# 01_POWER.net
KiCad netlist of a schematic drawn in Altium Designer
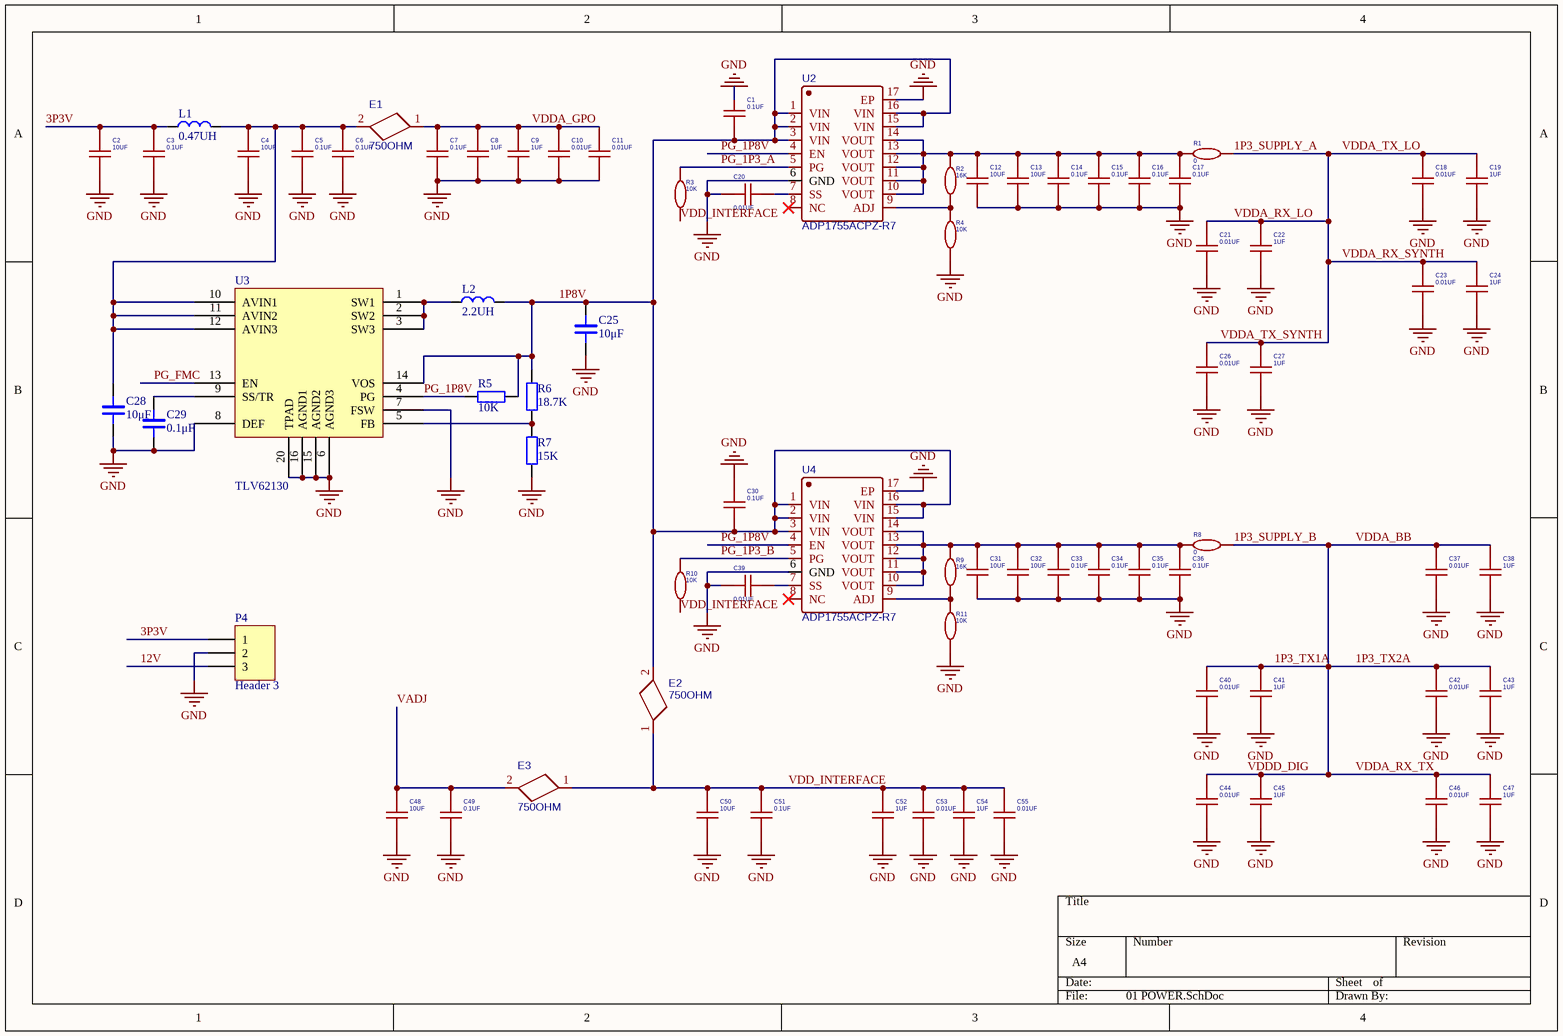
[diagram p0: 01 POWER.SchDoc]

(export (version "E")
  (design (tool "Eeschema 10.0.6"))
  (components
    (comp (ref "C1")
      (value "0.1UF")
      (footprint "C0402")
      (fields
        (field (name "BOM_MANUFACTURER PART") "0402B104K160")
        (field (name "BOM_SUPPLIER PART") "C83056")
      )
      (libsource (lib "pluto-7020CLG400") (part "0.1UF"))
    )
    (comp (ref "C2")
      (value "10UF")
      (footprint "C0402")
      (fields
        (field (name "BOM_MANUFACTURER PART") "0402B104K160")
        (field (name "BOM_SUPPLIER PART") "C83056")
      )
      (libsource (lib "pluto-7020CLG400") (part "10UF"))
    )
    (comp (ref "C3")
      (value "0.1UF")
      (footprint "C0402")
      (fields
        (field (name "BOM_MANUFACTURER PART") "0402B104K160")
        (field (name "BOM_SUPPLIER PART") "C83056")
      )
      (libsource (lib "pluto-7020CLG400") (part "0.1UF"))
    )
    (comp (ref "C4")
      (value "10UF")
      (footprint "C0402")
      (fields
        (field (name "BOM_MANUFACTURER PART") "0402B104K160")
        (field (name "BOM_SUPPLIER PART") "C83056")
      )
      (libsource (lib "pluto-7020CLG400") (part "10UF"))
    )
    (comp (ref "C5")
      (value "0.1UF")
      (footprint "C0402")
      (fields
        (field (name "BOM_MANUFACTURER PART") "0402B104K160")
        (field (name "BOM_SUPPLIER PART") "C83056")
      )
      (libsource (lib "pluto-7020CLG400") (part "0.1UF"))
    )
    (comp (ref "C6")
      (value "0.1UF")
      (footprint "C0402")
      (fields
        (field (name "BOM_MANUFACTURER PART") "0402B104K160")
        (field (name "BOM_SUPPLIER PART") "C83056")
      )
      (libsource (lib "pluto-7020CLG400") (part "0.1UF"))
    )
    (comp (ref "C7")
      (value "0.1UF")
      (footprint "C0402")
      (fields
        (field (name "BOM_MANUFACTURER PART") "0402B104K160")
        (field (name "BOM_SUPPLIER PART") "C83056")
      )
      (libsource (lib "pluto-7020CLG400") (part "0.1UF"))
    )
    (comp (ref "C8")
      (value "1UF")
      (footprint "C0402")
      (fields
        (field (name "BOM_MANUFACTURER PART") "0402B104K160")
        (field (name "BOM_SUPPLIER PART") "C83056")
      )
      (libsource (lib "pluto-7020CLG400") (part "10UF"))
    )
    (comp (ref "C9")
      (value "1UF")
      (footprint "C0402")
      (fields
        (field (name "BOM_MANUFACTURER PART") "0402B104K160")
        (field (name "BOM_SUPPLIER PART") "C83056")
      )
      (libsource (lib "pluto-7020CLG400") (part "10UF"))
    )
    (comp (ref "C10")
      (value "0.01UF")
      (footprint "C0201")
      (fields
        (field (name "BOM_MANUFACTURER PART") "0402B104K160")
        (field (name "BOM_SUPPLIER PART") "C83056")
      )
      (libsource (lib "pluto-7020CLG400") (part "10UF"))
    )
    (comp (ref "C11")
      (value "0.01UF")
      (footprint "C0201")
      (fields
        (field (name "BOM_MANUFACTURER PART") "0402B104K160")
        (field (name "BOM_SUPPLIER PART") "C83056")
      )
      (libsource (lib "pluto-7020CLG400") (part "10UF"))
    )
    (comp (ref "C12")
      (value "10UF")
      (footprint "C0402")
      (fields
        (field (name "BOM_MANUFACTURER PART") "0402B104K160")
        (field (name "BOM_SUPPLIER PART") "C83056")
      )
      (libsource (lib "pluto-7020CLG400") (part "10UF"))
    )
    (comp (ref "C13")
      (value "10UF")
      (footprint "C0402")
      (fields
        (field (name "BOM_MANUFACTURER PART") "0402B104K160")
        (field (name "BOM_SUPPLIER PART") "C83056")
      )
      (libsource (lib "pluto-7020CLG400") (part "10UF"))
    )
    (comp (ref "C14")
      (value "0.1UF")
      (footprint "C0402")
      (fields
        (field (name "BOM_MANUFACTURER PART") "0402B104K160")
        (field (name "BOM_SUPPLIER PART") "C83056")
      )
      (libsource (lib "pluto-7020CLG400") (part "0.1UF"))
    )
    (comp (ref "C15")
      (value "0.1UF")
      (footprint "C0402")
      (fields
        (field (name "BOM_MANUFACTURER PART") "0402B104K160")
        (field (name "BOM_SUPPLIER PART") "C83056")
      )
      (libsource (lib "pluto-7020CLG400") (part "0.1UF"))
    )
    (comp (ref "C16")
      (value "0.1UF")
      (footprint "C0402")
      (fields
        (field (name "BOM_MANUFACTURER PART") "0402B104K160")
        (field (name "BOM_SUPPLIER PART") "C83056")
      )
      (libsource (lib "pluto-7020CLG400") (part "0.1UF"))
    )
    (comp (ref "C17")
      (value "0.1UF")
      (footprint "C0402")
      (fields
        (field (name "BOM_MANUFACTURER PART") "0402B104K160")
        (field (name "BOM_SUPPLIER PART") "C83056")
      )
      (libsource (lib "pluto-7020CLG400") (part "0.1UF"))
    )
    (comp (ref "C18")
      (value "0.01UF")
      (footprint "C0201")
      (fields
        (field (name "BOM_MANUFACTURER PART") "0402B104K160")
        (field (name "BOM_SUPPLIER PART") "C83056")
      )
      (libsource (lib "pluto-7020CLG400") (part "10UF"))
    )
    (comp (ref "C19")
      (value "1UF")
      (footprint "C0402")
      (fields
        (field (name "BOM_MANUFACTURER PART") "0402B104K160")
        (field (name "BOM_SUPPLIER PART") "C83056")
      )
      (libsource (lib "pluto-7020CLG400") (part "10UF"))
    )
    (comp (ref "C20")
      (value "0.01UF")
      (footprint "C0201")
      (fields
        (field (name "BOM_MANUFACTURER PART") "0402B104K160")
        (field (name "BOM_SUPPLIER PART") "C83056")
      )
      (libsource (lib "pluto-7020CLG400") (part "0.01UF"))
    )
    (comp (ref "C21")
      (value "0.01UF")
      (footprint "C0201")
      (fields
        (field (name "BOM_MANUFACTURER PART") "0402B104K160")
        (field (name "BOM_SUPPLIER PART") "C83056")
      )
      (libsource (lib "pluto-7020CLG400") (part "10UF"))
    )
    (comp (ref "C22")
      (value "1UF")
      (footprint "C0402")
      (fields
        (field (name "BOM_MANUFACTURER PART") "0402B104K160")
        (field (name "BOM_SUPPLIER PART") "C83056")
      )
      (libsource (lib "pluto-7020CLG400") (part "10UF"))
    )
    (comp (ref "C23")
      (value "0.01UF")
      (footprint "C0201")
      (fields
        (field (name "BOM_MANUFACTURER PART") "0402B104K160")
        (field (name "BOM_SUPPLIER PART") "C83056")
      )
      (libsource (lib "pluto-7020CLG400") (part "10UF"))
    )
    (comp (ref "C24")
      (value "1UF")
      (footprint "C0402")
      (fields
        (field (name "BOM_MANUFACTURER PART") "0402B104K160")
        (field (name "BOM_SUPPLIER PART") "C83056")
      )
      (libsource (lib "pluto-7020CLG400") (part "10UF"))
    )
    (comp (ref "C25")
      (value "10μF")
      (footprint "C0402")
      (description "Capacitor")
      (libsource (lib "NGFF_M_Key_xc7z010-clg400") (part "CAP_3"))
    )
    (comp (ref "C26")
      (value "0.01UF")
      (footprint "C0201")
      (fields
        (field (name "BOM_MANUFACTURER PART") "0402B104K160")
        (field (name "BOM_SUPPLIER PART") "C83056")
      )
      (libsource (lib "pluto-7020CLG400") (part "10UF"))
    )
    (comp (ref "C27")
      (value "1UF")
      (footprint "C0402")
      (fields
        (field (name "BOM_MANUFACTURER PART") "0402B104K160")
        (field (name "BOM_SUPPLIER PART") "C83056")
      )
      (libsource (lib "pluto-7020CLG400") (part "10UF"))
    )
    (comp (ref "C28")
      (value "10μF")
      (footprint "C0402")
      (description "Capacitor")
      (libsource (lib "NGFF_M_Key_xc7z010-clg400") (part "CAP_3"))
    )
    (comp (ref "C29")
      (value "0.1μF")
      (footprint "C0402")
      (description "Capacitor")
      (libsource (lib "NGFF_M_Key_xc7z010-clg400") (part "CAP_3"))
    )
    (comp (ref "C30")
      (value "0.1UF")
      (footprint "C0402")
      (fields
        (field (name "BOM_MANUFACTURER PART") "0402B104K160")
        (field (name "BOM_SUPPLIER PART") "C83056")
      )
      (libsource (lib "pluto-7020CLG400") (part "0.1UF"))
    )
    (comp (ref "C31")
      (value "10UF")
      (footprint "C0402")
      (fields
        (field (name "BOM_MANUFACTURER PART") "0402B104K160")
        (field (name "BOM_SUPPLIER PART") "C83056")
      )
      (libsource (lib "pluto-7020CLG400") (part "10UF"))
    )
    (comp (ref "C32")
      (value "10UF")
      (footprint "C0402")
      (fields
        (field (name "BOM_MANUFACTURER PART") "0402B104K160")
        (field (name "BOM_SUPPLIER PART") "C83056")
      )
      (libsource (lib "pluto-7020CLG400") (part "10UF"))
    )
    (comp (ref "C33")
      (value "0.1UF")
      (footprint "C0402")
      (fields
        (field (name "BOM_MANUFACTURER PART") "0402B104K160")
        (field (name "BOM_SUPPLIER PART") "C83056")
      )
      (libsource (lib "pluto-7020CLG400") (part "0.1UF"))
    )
    (comp (ref "C34")
      (value "0.1UF")
      (footprint "C0402")
      (fields
        (field (name "BOM_MANUFACTURER PART") "0402B104K160")
        (field (name "BOM_SUPPLIER PART") "C83056")
      )
      (libsource (lib "pluto-7020CLG400") (part "0.1UF"))
    )
    (comp (ref "C35")
      (value "0.1UF")
      (footprint "C0402")
      (fields
        (field (name "BOM_MANUFACTURER PART") "0402B104K160")
        (field (name "BOM_SUPPLIER PART") "C83056")
      )
      (libsource (lib "pluto-7020CLG400") (part "0.1UF"))
    )
    (comp (ref "C36")
      (value "0.1UF")
      (footprint "C0402")
      (fields
        (field (name "BOM_MANUFACTURER PART") "0402B104K160")
        (field (name "BOM_SUPPLIER PART") "C83056")
      )
      (libsource (lib "pluto-7020CLG400") (part "0.1UF"))
    )
    (comp (ref "C37")
      (value "0.01UF")
      (footprint "C0402")
      (fields
        (field (name "BOM_MANUFACTURER PART") "0402B104K160")
        (field (name "BOM_SUPPLIER PART") "C83056")
      )
      (libsource (lib "pluto-7020CLG400") (part "10UF"))
    )
    (comp (ref "C38")
      (value "1UF")
      (footprint "C0402")
      (fields
        (field (name "BOM_MANUFACTURER PART") "0402B104K160")
        (field (name "BOM_SUPPLIER PART") "C83056")
      )
      (libsource (lib "pluto-7020CLG400") (part "10UF"))
    )
    (comp (ref "C39")
      (value "0.01UF")
      (footprint "C0402")
      (fields
        (field (name "BOM_MANUFACTURER PART") "0402B104K160")
        (field (name "BOM_SUPPLIER PART") "C83056")
      )
      (libsource (lib "pluto-7020CLG400") (part "0.01UF"))
    )
    (comp (ref "C40")
      (value "0.01UF")
      (footprint "C0402")
      (fields
        (field (name "BOM_MANUFACTURER PART") "0402B104K160")
        (field (name "BOM_SUPPLIER PART") "C83056")
      )
      (libsource (lib "pluto-7020CLG400") (part "10UF"))
    )
    (comp (ref "C41")
      (value "1UF")
      (footprint "C0402")
      (fields
        (field (name "BOM_MANUFACTURER PART") "0402B104K160")
        (field (name "BOM_SUPPLIER PART") "C83056")
      )
      (libsource (lib "pluto-7020CLG400") (part "10UF"))
    )
    (comp (ref "C42")
      (value "0.01UF")
      (footprint "C0201")
      (fields
        (field (name "BOM_MANUFACTURER PART") "0402B104K160")
        (field (name "BOM_SUPPLIER PART") "C83056")
      )
      (libsource (lib "pluto-7020CLG400") (part "10UF"))
    )
    (comp (ref "C43")
      (value "1UF")
      (footprint "C0402")
      (fields
        (field (name "BOM_MANUFACTURER PART") "0402B104K160")
        (field (name "BOM_SUPPLIER PART") "C83056")
      )
      (libsource (lib "pluto-7020CLG400") (part "10UF"))
    )
    (comp (ref "C44")
      (value "0.01UF")
      (footprint "C0201")
      (fields
        (field (name "BOM_MANUFACTURER PART") "0402B104K160")
        (field (name "BOM_SUPPLIER PART") "C83056")
      )
      (libsource (lib "pluto-7020CLG400") (part "10UF"))
    )
    (comp (ref "C45")
      (value "1UF")
      (footprint "C0402")
      (fields
        (field (name "BOM_MANUFACTURER PART") "0402B104K160")
        (field (name "BOM_SUPPLIER PART") "C83056")
      )
      (libsource (lib "pluto-7020CLG400") (part "10UF"))
    )
    (comp (ref "C46")
      (value "0.01UF")
      (footprint "C0402")
      (fields
        (field (name "BOM_MANUFACTURER PART") "0402B104K160")
        (field (name "BOM_SUPPLIER PART") "C83056")
      )
      (libsource (lib "pluto-7020CLG400") (part "10UF"))
    )
    (comp (ref "C47")
      (value "1UF")
      (footprint "C0402")
      (fields
        (field (name "BOM_MANUFACTURER PART") "0402B104K160")
        (field (name "BOM_SUPPLIER PART") "C83056")
      )
      (libsource (lib "pluto-7020CLG400") (part "10UF"))
    )
    (comp (ref "C48")
      (value "10UF")
      (footprint "C0603")
      (fields
        (field (name "BOM_MANUFACTURER PART") "0402B104K160")
        (field (name "BOM_SUPPLIER PART") "C83056")
      )
      (libsource (lib "pluto-7020CLG400") (part "10UF"))
    )
    (comp (ref "C49")
      (value "0.1UF")
      (footprint "C0402")
      (fields
        (field (name "BOM_MANUFACTURER PART") "0402B104K160")
        (field (name "BOM_SUPPLIER PART") "C83056")
      )
      (libsource (lib "pluto-7020CLG400") (part "0.1UF"))
    )
    (comp (ref "C50")
      (value "10UF")
      (footprint "C0402")
      (fields
        (field (name "BOM_MANUFACTURER PART") "0402B104K160")
        (field (name "BOM_SUPPLIER PART") "C83056")
      )
      (libsource (lib "pluto-7020CLG400") (part "10UF"))
    )
    (comp (ref "C51")
      (value "0.1UF")
      (footprint "C0201")
      (fields
        (field (name "BOM_MANUFACTURER PART") "0402B104K160")
        (field (name "BOM_SUPPLIER PART") "C83056")
      )
      (libsource (lib "pluto-7020CLG400") (part "0.1UF"))
    )
    (comp (ref "C52")
      (value "1UF")
      (footprint "C0402")
      (fields
        (field (name "BOM_MANUFACTURER PART") "0402B104K160")
        (field (name "BOM_SUPPLIER PART") "C83056")
      )
      (libsource (lib "pluto-7020CLG400") (part "10UF"))
    )
    (comp (ref "C53")
      (value "0.01UF")
      (footprint "C0201")
      (fields
        (field (name "BOM_MANUFACTURER PART") "0402B104K160")
        (field (name "BOM_SUPPLIER PART") "C83056")
      )
      (libsource (lib "pluto-7020CLG400") (part "10UF"))
    )
    (comp (ref "C54")
      (value "1UF")
      (footprint "C0402")
      (fields
        (field (name "BOM_MANUFACTURER PART") "0402B104K160")
        (field (name "BOM_SUPPLIER PART") "C83056")
      )
      (libsource (lib "pluto-7020CLG400") (part "10UF"))
    )
    (comp (ref "C55")
      (value "0.01UF")
      (footprint "C0201")
      (fields
        (field (name "BOM_MANUFACTURER PART") "0402B104K160")
        (field (name "BOM_SUPPLIER PART") "C83056")
      )
      (libsource (lib "pluto-7020CLG400") (part "10UF"))
    )
    (comp (ref "E1")
      (value "750OHM")
      (footprint "L0402")
      (fields (field (name "BOM_MANUFACTURER PART") "BLM21PG221SN1x") (field (name "CONTRIBUTOR") "prophetC"))
      (libsource (lib "pluto-7020CLG400") (part "100OHM"))
    )
    (comp (ref "E2")
      (value "750OHM")
      (footprint "L0402")
      (fields (field (name "BOM_MANUFACTURER PART") "BLM21PG221SN1x") (field (name "CONTRIBUTOR") "prophetC"))
      (libsource (lib "pluto-7020CLG400") (part "100OHM"))
    )
    (comp (ref "E3")
      (value "750OHM")
      (footprint "L0402")
      (fields (field (name "BOM_MANUFACTURER PART") "BLM21PG221SN1x") (field (name "CONTRIBUTOR") "prophetC"))
      (libsource (lib "pluto-7020CLG400") (part "100OHM"))
    )
    (comp (ref "L1")
      (value "0.47UH")
      (footprint "L1008")
      (description "Inductance")
      (libsource (lib "NGFF_M_Key_xc7z010-clg400") (part "INDUCTANCE_1"))
    )
    (comp (ref "L2")
      (value "2.2UH")
      (footprint "L1008")
      (description "Inductance")
      (libsource (lib "NGFF_M_Key_xc7z010-clg400") (part "INDUCTANCE_1"))
    )
    (comp (ref "P4")
      (value "Header 3")
      (footprint "CNBERG1X3H205LD36")
      (description "Header, 3-Pin")
      (fields (field (name "PUBLISHER") "Altium Limited"))
      (libsource (lib "Miscellaneous Connectors") (part "Header 3"))
    )
    (comp (ref "R1")
      (value "0")
      (footprint "R1206")
      (fields
        (field (name "BOM_SUPPLIER PART") "C185392")
        (field (name "BOM_MANUFACTURER PART") "RC0402FR-0780R6L")
        (field (name "CONTRIBUTOR") "LCSC")
      )
      (libsource (lib "pluto-7020CLG400") (part "1"))
    )
    (comp (ref "R2")
      (value "16K")
      (footprint "LC-0402_R")
      (fields
        (field (name "BOM_SUPPLIER PART") "C185392")
        (field (name "BOM_MANUFACTURER PART") "RC0402FR-0780R6L")
        (field (name "CONTRIBUTOR") "LCSC")
      )
      (libsource (lib "pluto-7020CLG400") (part "10K"))
    )
    (comp (ref "R3")
      (value "10K")
      (footprint "C0201")
      (fields
        (field (name "BOM_SUPPLIER PART") "C185392")
        (field (name "BOM_MANUFACTURER PART") "RC0402FR-0780R6L")
        (field (name "CONTRIBUTOR") "LCSC")
      )
      (libsource (lib "pluto-7020CLG400") (part "10K"))
    )
    (comp (ref "R4")
      (value "10K")
      (footprint "LC-0402_R")
      (fields
        (field (name "BOM_SUPPLIER PART") "C185392")
        (field (name "BOM_MANUFACTURER PART") "RC0402FR-0780R6L")
        (field (name "CONTRIBUTOR") "LCSC")
      )
      (libsource (lib "pluto-7020CLG400") (part "10K"))
    )
    (comp (ref "R5")
      (value "10K")
      (footprint "LC-0402_R")
      (description "Resistor")
      (libsource (lib "NGFF_M_Key_xc7z010-clg400") (part "RES"))
    )
    (comp (ref "R6")
      (value "18.7K")
      (footprint "LC-0402_R")
      (description "Resistor")
      (libsource (lib "") (part "RES_1"))
    )
    (comp (ref "R7")
      (value "15K")
      (footprint "LC-0402_R")
      (description "Resistor")
      (libsource (lib "") (part "RES_1"))
    )
    (comp (ref "R8")
      (value "0")
      (footprint "R1206")
      (fields
        (field (name "BOM_SUPPLIER PART") "C185392")
        (field (name "BOM_MANUFACTURER PART") "RC0402FR-0780R6L")
        (field (name "CONTRIBUTOR") "LCSC")
      )
      (libsource (lib "pluto-7020CLG400") (part "1"))
    )
    (comp (ref "R9")
      (value "16K")
      (footprint "LC-0402_R")
      (fields
        (field (name "BOM_SUPPLIER PART") "C185392")
        (field (name "BOM_MANUFACTURER PART") "RC0402FR-0780R6L")
        (field (name "CONTRIBUTOR") "LCSC")
      )
      (libsource (lib "pluto-7020CLG400") (part "10K"))
    )
    (comp (ref "R10")
      (value "10K")
      (footprint "LC-0402_R")
      (fields
        (field (name "BOM_SUPPLIER PART") "C185392")
        (field (name "BOM_MANUFACTURER PART") "RC0402FR-0780R6L")
        (field (name "CONTRIBUTOR") "LCSC")
      )
      (libsource (lib "pluto-7020CLG400") (part "10K"))
    )
    (comp (ref "R11")
      (value "10K")
      (footprint "LC-0402_R")
      (fields
        (field (name "BOM_SUPPLIER PART") "C185392")
        (field (name "BOM_MANUFACTURER PART") "RC0402FR-0780R6L")
        (field (name "CONTRIBUTOR") "LCSC")
      )
      (libsource (lib "pluto-7020CLG400") (part "10K"))
    )
    (comp (ref "U2")
      (value "ADP1755ACPZ-R7")
      (footprint "LFCSP-WQ-16_L4.0-W4.0-P0.65-EP2.3-BL-EP")
      (fields (field (name "BOM_SUPPLIER PART") "C403695") (field (name "CONTRIBUTOR") "LCSC"))
      (libsource (lib "demo_fmccomms3") (part "ADP1755ACPZ-R7"))
    )
    (comp (ref "U3")
      (value "TLV62130")
      (footprint "TLV62130RGT")
      (libsource (lib "PCB_Project") (part "TLV62130"))
    )
    (comp (ref "U4")
      (value "ADP1755ACPZ-R7")
      (footprint "LFCSP-WQ-16_L4.0-W4.0-P0.65-EP2.3-BL-EP")
      (fields (field (name "BOM_SUPPLIER PART") "C403695") (field (name "CONTRIBUTOR") "LCSC"))
      (libsource (lib "demo_fmccomms3") (part "ADP1755ACPZ-R7"))
    )
  )
  (nets
    (net (code "1") (name "/1P3_SUPPLY_A") (class "Default")
      (node (ref "C18") (pin "1") (pinfunction "1_1") (pintype "passive"))
      (node (ref "C19") (pin "1") (pinfunction "1_1") (pintype "passive"))
      (node (ref "C21") (pin "1") (pinfunction "1_1") (pintype "passive"))
      (node (ref "C22") (pin "1") (pinfunction "1_1") (pintype "passive"))
      (node (ref "C23") (pin "1") (pinfunction "1_1") (pintype "passive"))
      (node (ref "C24") (pin "1") (pinfunction "1_1") (pintype "passive"))
      (node (ref "C26") (pin "1") (pinfunction "1_1") (pintype "passive"))
      (node (ref "C27") (pin "1") (pinfunction "1_1") (pintype "passive"))
      (node (ref "R1") (pin "2") (pinfunction "2_2") (pintype "passive"))
    )
    (net (code "2") (name "/1P3_SUPPLY_B") (class "Default")
      (node (ref "C37") (pin "1") (pinfunction "1_1") (pintype "passive"))
      (node (ref "C38") (pin "1") (pinfunction "1_1") (pintype "passive"))
      (node (ref "C40") (pin "1") (pinfunction "1_1") (pintype "passive"))
      (node (ref "C41") (pin "1") (pinfunction "1_1") (pintype "passive"))
      (node (ref "C42") (pin "1") (pinfunction "1_1") (pintype "passive"))
      (node (ref "C43") (pin "1") (pinfunction "1_1") (pintype "passive"))
      (node (ref "C44") (pin "1") (pinfunction "1_1") (pintype "passive"))
      (node (ref "C45") (pin "1") (pinfunction "1_1") (pintype "passive"))
      (node (ref "C46") (pin "1") (pinfunction "1_1") (pintype "passive"))
      (node (ref "C47") (pin "1") (pinfunction "1_1") (pintype "passive"))
      (node (ref "R8") (pin "2") (pinfunction "2_2") (pintype "passive"))
    )
    (net (code "3") (name "/1P8V") (class "Default")
      (node (ref "C1") (pin "2") (pinfunction "2_2") (pintype "passive"))
      (node (ref "C25") (pin "2") (pinfunction "2_2") (pintype "passive"))
      (node (ref "C30") (pin "2") (pinfunction "2_2") (pintype "passive"))
      (node (ref "E2") (pin "2") (pinfunction "2_2") (pintype "passive"))
      (node (ref "L2") (pin "2") (pinfunction "2_2") (pintype "passive"))
      (node (ref "R5") (pin "1") (pinfunction "1_1") (pintype "passive"))
      (node (ref "R6") (pin "1") (pinfunction "1_1") (pintype "passive"))
      (node (ref "U2") (pin "1") (pinfunction "VIN_1") (pintype "passive"))
      (node (ref "U2") (pin "15") (pinfunction "VIN_15") (pintype "passive"))
      (node (ref "U2") (pin "16") (pinfunction "VIN_16") (pintype "passive"))
      (node (ref "U2") (pin "2") (pinfunction "VIN_2") (pintype "passive"))
      (node (ref "U2") (pin "3") (pinfunction "VIN_3") (pintype "passive"))
      (node (ref "U3") (pin "14") (pinfunction "VOS_14") (pintype "passive"))
      (node (ref "U4") (pin "1") (pinfunction "VIN_1") (pintype "passive"))
      (node (ref "U4") (pin "15") (pinfunction "VIN_15") (pintype "passive"))
      (node (ref "U4") (pin "16") (pinfunction "VIN_16") (pintype "passive"))
      (node (ref "U4") (pin "2") (pinfunction "VIN_2") (pintype "passive"))
      (node (ref "U4") (pin "3") (pinfunction "VIN_3") (pintype "passive"))
    )
    (net (code "4") (name "/3P3V") (class "Default")
      (node (ref "C2") (pin "1") (pinfunction "1_1") (pintype "passive"))
      (node (ref "C3") (pin "1") (pinfunction "1_1") (pintype "passive"))
      (node (ref "L1") (pin "1") (pinfunction "1_1") (pintype "passive"))
      (node (ref "P4") (pin "1") (pinfunction "1_1") (pintype "passive"))
    )
    (net (code "5") (name "/12V") (class "Default")
      (node (ref "P4") (pin "3") (pinfunction "3_3") (pintype "passive"))
    )
    (net (code "6") (name "/PG_1P3_A") (class "Default")
      (node (ref "R3") (pin "2") (pinfunction "2_2") (pintype "passive"))
      (node (ref "U2") (pin "5") (pinfunction "PG_5") (pintype "passive"))
    )
    (net (code "7") (name "/PG_1P3_B") (class "Default")
      (node (ref "R10") (pin "2") (pinfunction "2_2") (pintype "passive"))
      (node (ref "U4") (pin "5") (pinfunction "PG_5") (pintype "passive"))
    )
    (net (code "8") (name "/PG_1P8V") (class "Default")
      (node (ref "R5") (pin "2") (pinfunction "2_2") (pintype "passive"))
      (node (ref "U2") (pin "4") (pinfunction "EN_4") (pintype "passive"))
      (node (ref "U3") (pin "4") (pinfunction "PG_4") (pintype "passive"))
      (node (ref "U4") (pin "4") (pinfunction "EN_4") (pintype "passive"))
    )
    (net (code "9") (name "/PG_FMC") (class "Default")
      (node (ref "U3") (pin "13") (pinfunction "EN_13") (pintype "passive"))
    )
    (net (code "10") (name "/VADJ") (class "Default")
      (node (ref "C48") (pin "1") (pinfunction "1_1") (pintype "passive"))
      (node (ref "C49") (pin "1") (pinfunction "1_1") (pintype "passive"))
      (node (ref "E3") (pin "2") (pinfunction "2_2") (pintype "passive"))
    )
    (net (code "11") (name "/VDDA_GPO") (class "Default")
      (node (ref "C10") (pin "1") (pinfunction "1_1") (pintype "passive"))
      (node (ref "C11") (pin "1") (pinfunction "1_1") (pintype "passive"))
      (node (ref "C7") (pin "1") (pinfunction "1_1") (pintype "passive"))
      (node (ref "C8") (pin "1") (pinfunction "1_1") (pintype "passive"))
      (node (ref "C9") (pin "1") (pinfunction "1_1") (pintype "passive"))
      (node (ref "E1") (pin "1") (pinfunction "1_1") (pintype "passive"))
    )
    (net (code "12") (name "/VDD_INTERFACE") (class "Default")
      (node (ref "C50") (pin "1") (pinfunction "1_1") (pintype "passive"))
      (node (ref "C51") (pin "1") (pinfunction "1_1") (pintype "passive"))
      (node (ref "C52") (pin "1") (pinfunction "1_1") (pintype "passive"))
      (node (ref "C53") (pin "1") (pinfunction "1_1") (pintype "passive"))
      (node (ref "C54") (pin "1") (pinfunction "1_1") (pintype "passive"))
      (node (ref "C55") (pin "1") (pinfunction "1_1") (pintype "passive"))
      (node (ref "E2") (pin "1") (pinfunction "1_1") (pintype "passive"))
      (node (ref "E3") (pin "1") (pinfunction "1_1") (pintype "passive"))
      (node (ref "R10") (pin "1") (pinfunction "1_1") (pintype "passive"))
      (node (ref "R3") (pin "1") (pinfunction "1_1") (pintype "passive"))
    )
    (net (code "13") (name "GND") (class "Default")
      (node (ref "C1") (pin "1") (pinfunction "1_1") (pintype "passive"))
      (node (ref "C10") (pin "2") (pinfunction "2_2") (pintype "passive"))
      (node (ref "C11") (pin "2") (pinfunction "2_2") (pintype "passive"))
      (node (ref "C12") (pin "2") (pinfunction "2_2") (pintype "passive"))
      (node (ref "C13") (pin "2") (pinfunction "2_2") (pintype "passive"))
      (node (ref "C14") (pin "2") (pinfunction "2_2") (pintype "passive"))
      (node (ref "C15") (pin "2") (pinfunction "2_2") (pintype "passive"))
      (node (ref "C16") (pin "2") (pinfunction "2_2") (pintype "passive"))
      (node (ref "C17") (pin "2") (pinfunction "2_2") (pintype "passive"))
      (node (ref "C18") (pin "2") (pinfunction "2_2") (pintype "passive"))
      (node (ref "C19") (pin "2") (pinfunction "2_2") (pintype "passive"))
      (node (ref "C2") (pin "2") (pinfunction "2_2") (pintype "passive"))
      (node (ref "C20") (pin "2") (pinfunction "2_2") (pintype "passive"))
      (node (ref "C21") (pin "2") (pinfunction "2_2") (pintype "passive"))
      (node (ref "C22") (pin "2") (pinfunction "2_2") (pintype "passive"))
      (node (ref "C23") (pin "2") (pinfunction "2_2") (pintype "passive"))
      (node (ref "C24") (pin "2") (pinfunction "2_2") (pintype "passive"))
      (node (ref "C25") (pin "1") (pinfunction "1_1") (pintype "passive"))
      (node (ref "C26") (pin "2") (pinfunction "2_2") (pintype "passive"))
      (node (ref "C27") (pin "2") (pinfunction "2_2") (pintype "passive"))
      (node (ref "C28") (pin "1") (pinfunction "1_1") (pintype "passive"))
      (node (ref "C29") (pin "1") (pinfunction "1_1") (pintype "passive"))
      (node (ref "C3") (pin "2") (pinfunction "2_2") (pintype "passive"))
      (node (ref "C30") (pin "1") (pinfunction "1_1") (pintype "passive"))
      (node (ref "C31") (pin "2") (pinfunction "2_2") (pintype "passive"))
      (node (ref "C32") (pin "2") (pinfunction "2_2") (pintype "passive"))
      (node (ref "C33") (pin "2") (pinfunction "2_2") (pintype "passive"))
      (node (ref "C34") (pin "2") (pinfunction "2_2") (pintype "passive"))
      (node (ref "C35") (pin "2") (pinfunction "2_2") (pintype "passive"))
      (node (ref "C36") (pin "2") (pinfunction "2_2") (pintype "passive"))
      (node (ref "C37") (pin "2") (pinfunction "2_2") (pintype "passive"))
      (node (ref "C38") (pin "2") (pinfunction "2_2") (pintype "passive"))
      (node (ref "C39") (pin "2") (pinfunction "2_2") (pintype "passive"))
      (node (ref "C4") (pin "2") (pinfunction "2_2") (pintype "passive"))
      (node (ref "C40") (pin "2") (pinfunction "2_2") (pintype "passive"))
      (node (ref "C41") (pin "2") (pinfunction "2_2") (pintype "passive"))
      (node (ref "C42") (pin "2") (pinfunction "2_2") (pintype "passive"))
      (node (ref "C43") (pin "2") (pinfunction "2_2") (pintype "passive"))
      (node (ref "C44") (pin "2") (pinfunction "2_2") (pintype "passive"))
      (node (ref "C45") (pin "2") (pinfunction "2_2") (pintype "passive"))
      (node (ref "C46") (pin "2") (pinfunction "2_2") (pintype "passive"))
      (node (ref "C47") (pin "2") (pinfunction "2_2") (pintype "passive"))
      (node (ref "C48") (pin "2") (pinfunction "2_2") (pintype "passive"))
      (node (ref "C49") (pin "2") (pinfunction "2_2") (pintype "passive"))
      (node (ref "C5") (pin "2") (pinfunction "2_2") (pintype "passive"))
      (node (ref "C50") (pin "2") (pinfunction "2_2") (pintype "passive"))
      (node (ref "C51") (pin "2") (pinfunction "2_2") (pintype "passive"))
      (node (ref "C52") (pin "2") (pinfunction "2_2") (pintype "passive"))
      (node (ref "C53") (pin "2") (pinfunction "2_2") (pintype "passive"))
      (node (ref "C54") (pin "2") (pinfunction "2_2") (pintype "passive"))
      (node (ref "C55") (pin "2") (pinfunction "2_2") (pintype "passive"))
      (node (ref "C6") (pin "2") (pinfunction "2_2") (pintype "passive"))
      (node (ref "C7") (pin "2") (pinfunction "2_2") (pintype "passive"))
      (node (ref "C8") (pin "2") (pinfunction "2_2") (pintype "passive"))
      (node (ref "C9") (pin "2") (pinfunction "2_2") (pintype "passive"))
      (node (ref "P4") (pin "2") (pinfunction "2_2") (pintype "passive"))
      (node (ref "R11") (pin "1") (pinfunction "1_1") (pintype "passive"))
      (node (ref "R4") (pin "1") (pinfunction "1_1") (pintype "passive"))
      (node (ref "R7") (pin "2") (pinfunction "2_2") (pintype "passive"))
      (node (ref "U2") (pin "17") (pinfunction "EP_17") (pintype "passive"))
      (node (ref "U2") (pin "6") (pinfunction "GND_6") (pintype "passive"))
      (node (ref "U3") (pin "15") (pinfunction "AGND2_15") (pintype "passive"))
      (node (ref "U3") (pin "16") (pinfunction "AGND1_16") (pintype "passive"))
      (node (ref "U3") (pin "20") (pinfunction "TPAD_20") (pintype "passive"))
      (node (ref "U3") (pin "6") (pinfunction "AGND3_6") (pintype "passive"))
      (node (ref "U3") (pin "7") (pinfunction "FSW_7") (pintype "passive"))
      (node (ref "U3") (pin "8") (pinfunction "DEF_8") (pintype "passive"))
      (node (ref "U4") (pin "17") (pinfunction "EP_17") (pintype "passive"))
      (node (ref "U4") (pin "6") (pinfunction "GND_6") (pintype "passive"))
    )
    (net (code "14") (name "Net-(C12-Pad1)") (class "Default")
      (node (ref "C12") (pin "1") (pinfunction "1_1") (pintype "passive"))
      (node (ref "C13") (pin "1") (pinfunction "1_1") (pintype "passive"))
      (node (ref "C14") (pin "1") (pinfunction "1_1") (pintype "passive"))
      (node (ref "C15") (pin "1") (pinfunction "1_1") (pintype "passive"))
      (node (ref "C16") (pin "1") (pinfunction "1_1") (pintype "passive"))
      (node (ref "C17") (pin "1") (pinfunction "1_1") (pintype "passive"))
      (node (ref "R1") (pin "1") (pinfunction "1_1") (pintype "passive"))
      (node (ref "R2") (pin "2") (pinfunction "2_2") (pintype "passive"))
      (node (ref "U2") (pin "10") (pinfunction "VOUT_10") (pintype "passive"))
      (node (ref "U2") (pin "11") (pinfunction "VOUT_11") (pintype "passive"))
      (node (ref "U2") (pin "12") (pinfunction "VOUT_12") (pintype "passive"))
      (node (ref "U2") (pin "13") (pinfunction "VOUT_13") (pintype "passive"))
      (node (ref "U2") (pin "14") (pinfunction "VOUT_14") (pintype "passive"))
    )
    (net (code "15") (name "Net-(C31-Pad1)") (class "Default")
      (node (ref "C31") (pin "1") (pinfunction "1_1") (pintype "passive"))
      (node (ref "C32") (pin "1") (pinfunction "1_1") (pintype "passive"))
      (node (ref "C33") (pin "1") (pinfunction "1_1") (pintype "passive"))
      (node (ref "C34") (pin "1") (pinfunction "1_1") (pintype "passive"))
      (node (ref "C35") (pin "1") (pinfunction "1_1") (pintype "passive"))
      (node (ref "C36") (pin "1") (pinfunction "1_1") (pintype "passive"))
      (node (ref "R8") (pin "1") (pinfunction "1_1") (pintype "passive"))
      (node (ref "R9") (pin "2") (pinfunction "2_2") (pintype "passive"))
      (node (ref "U4") (pin "10") (pinfunction "VOUT_10") (pintype "passive"))
      (node (ref "U4") (pin "11") (pinfunction "VOUT_11") (pintype "passive"))
      (node (ref "U4") (pin "12") (pinfunction "VOUT_12") (pintype "passive"))
      (node (ref "U4") (pin "13") (pinfunction "VOUT_13") (pintype "passive"))
      (node (ref "U4") (pin "14") (pinfunction "VOUT_14") (pintype "passive"))
    )
    (net (code "16") (name "Net-(U2-ADJ)") (class "Default")
      (node (ref "R2") (pin "1") (pinfunction "1_1") (pintype "passive"))
      (node (ref "R4") (pin "2") (pinfunction "2_2") (pintype "passive"))
      (node (ref "U2") (pin "9") (pinfunction "ADJ_9") (pintype "passive"))
    )
    (net (code "17") (name "Net-(U2-SS)") (class "Default")
      (node (ref "C20") (pin "1") (pinfunction "1_1") (pintype "passive"))
      (node (ref "U2") (pin "7") (pinfunction "SS_7") (pintype "passive"))
    )
    (net (code "18") (name "Net-(U3-AVIN1)") (class "Default")
      (node (ref "C28") (pin "2") (pinfunction "2_2") (pintype "passive"))
      (node (ref "C4") (pin "1") (pinfunction "1_1") (pintype "passive"))
      (node (ref "C5") (pin "1") (pinfunction "1_1") (pintype "passive"))
      (node (ref "C6") (pin "1") (pinfunction "1_1") (pintype "passive"))
      (node (ref "E1") (pin "2") (pinfunction "2_2") (pintype "passive"))
      (node (ref "L1") (pin "2") (pinfunction "2_2") (pintype "passive"))
      (node (ref "U3") (pin "10") (pinfunction "AVIN1_10") (pintype "passive"))
      (node (ref "U3") (pin "11") (pinfunction "AVIN2_11") (pintype "passive"))
      (node (ref "U3") (pin "12") (pinfunction "AVIN3_12") (pintype "passive"))
    )
    (net (code "19") (name "Net-(U3-FB)") (class "Default")
      (node (ref "R6") (pin "2") (pinfunction "2_2") (pintype "passive"))
      (node (ref "R7") (pin "1") (pinfunction "1_1") (pintype "passive"))
      (node (ref "U3") (pin "5") (pinfunction "FB_5") (pintype "passive"))
    )
    (net (code "20") (name "Net-(U3-SS{slash}TR)") (class "Default")
      (node (ref "C29") (pin "2") (pinfunction "2_2") (pintype "passive"))
      (node (ref "U3") (pin "9") (pinfunction "SS/TR_9") (pintype "passive"))
    )
    (net (code "21") (name "Net-(U3-SW1)") (class "Default")
      (node (ref "L2") (pin "1") (pinfunction "1_1") (pintype "passive"))
      (node (ref "U3") (pin "1") (pinfunction "SW1_1") (pintype "passive"))
      (node (ref "U3") (pin "2") (pinfunction "SW2_2") (pintype "passive"))
      (node (ref "U3") (pin "3") (pinfunction "SW3_3") (pintype "passive"))
    )
    (net (code "22") (name "Net-(U4-ADJ)") (class "Default")
      (node (ref "R11") (pin "2") (pinfunction "2_2") (pintype "passive"))
      (node (ref "R9") (pin "1") (pinfunction "1_1") (pintype "passive"))
      (node (ref "U4") (pin "9") (pinfunction "ADJ_9") (pintype "passive"))
    )
    (net (code "23") (name "Net-(U4-SS)") (class "Default")
      (node (ref "C39") (pin "1") (pinfunction "1_1") (pintype "passive"))
      (node (ref "U4") (pin "7") (pinfunction "SS_7") (pintype "passive"))
    )
    (net (code "24") (name "unconnected-(U2-NC-Pad8)") (class "Default")
      (node (ref "U2") (pin "8") (pinfunction "NC_8") (pintype "passive+no_connect"))
    )
    (net (code "25") (name "unconnected-(U4-NC-Pad8)") (class "Default")
      (node (ref "U4") (pin "8") (pinfunction "NC_8") (pintype "passive+no_connect"))
    )
  )
)
